# solohm.net
KiCad netlist of a schematic drawn in EAGLE
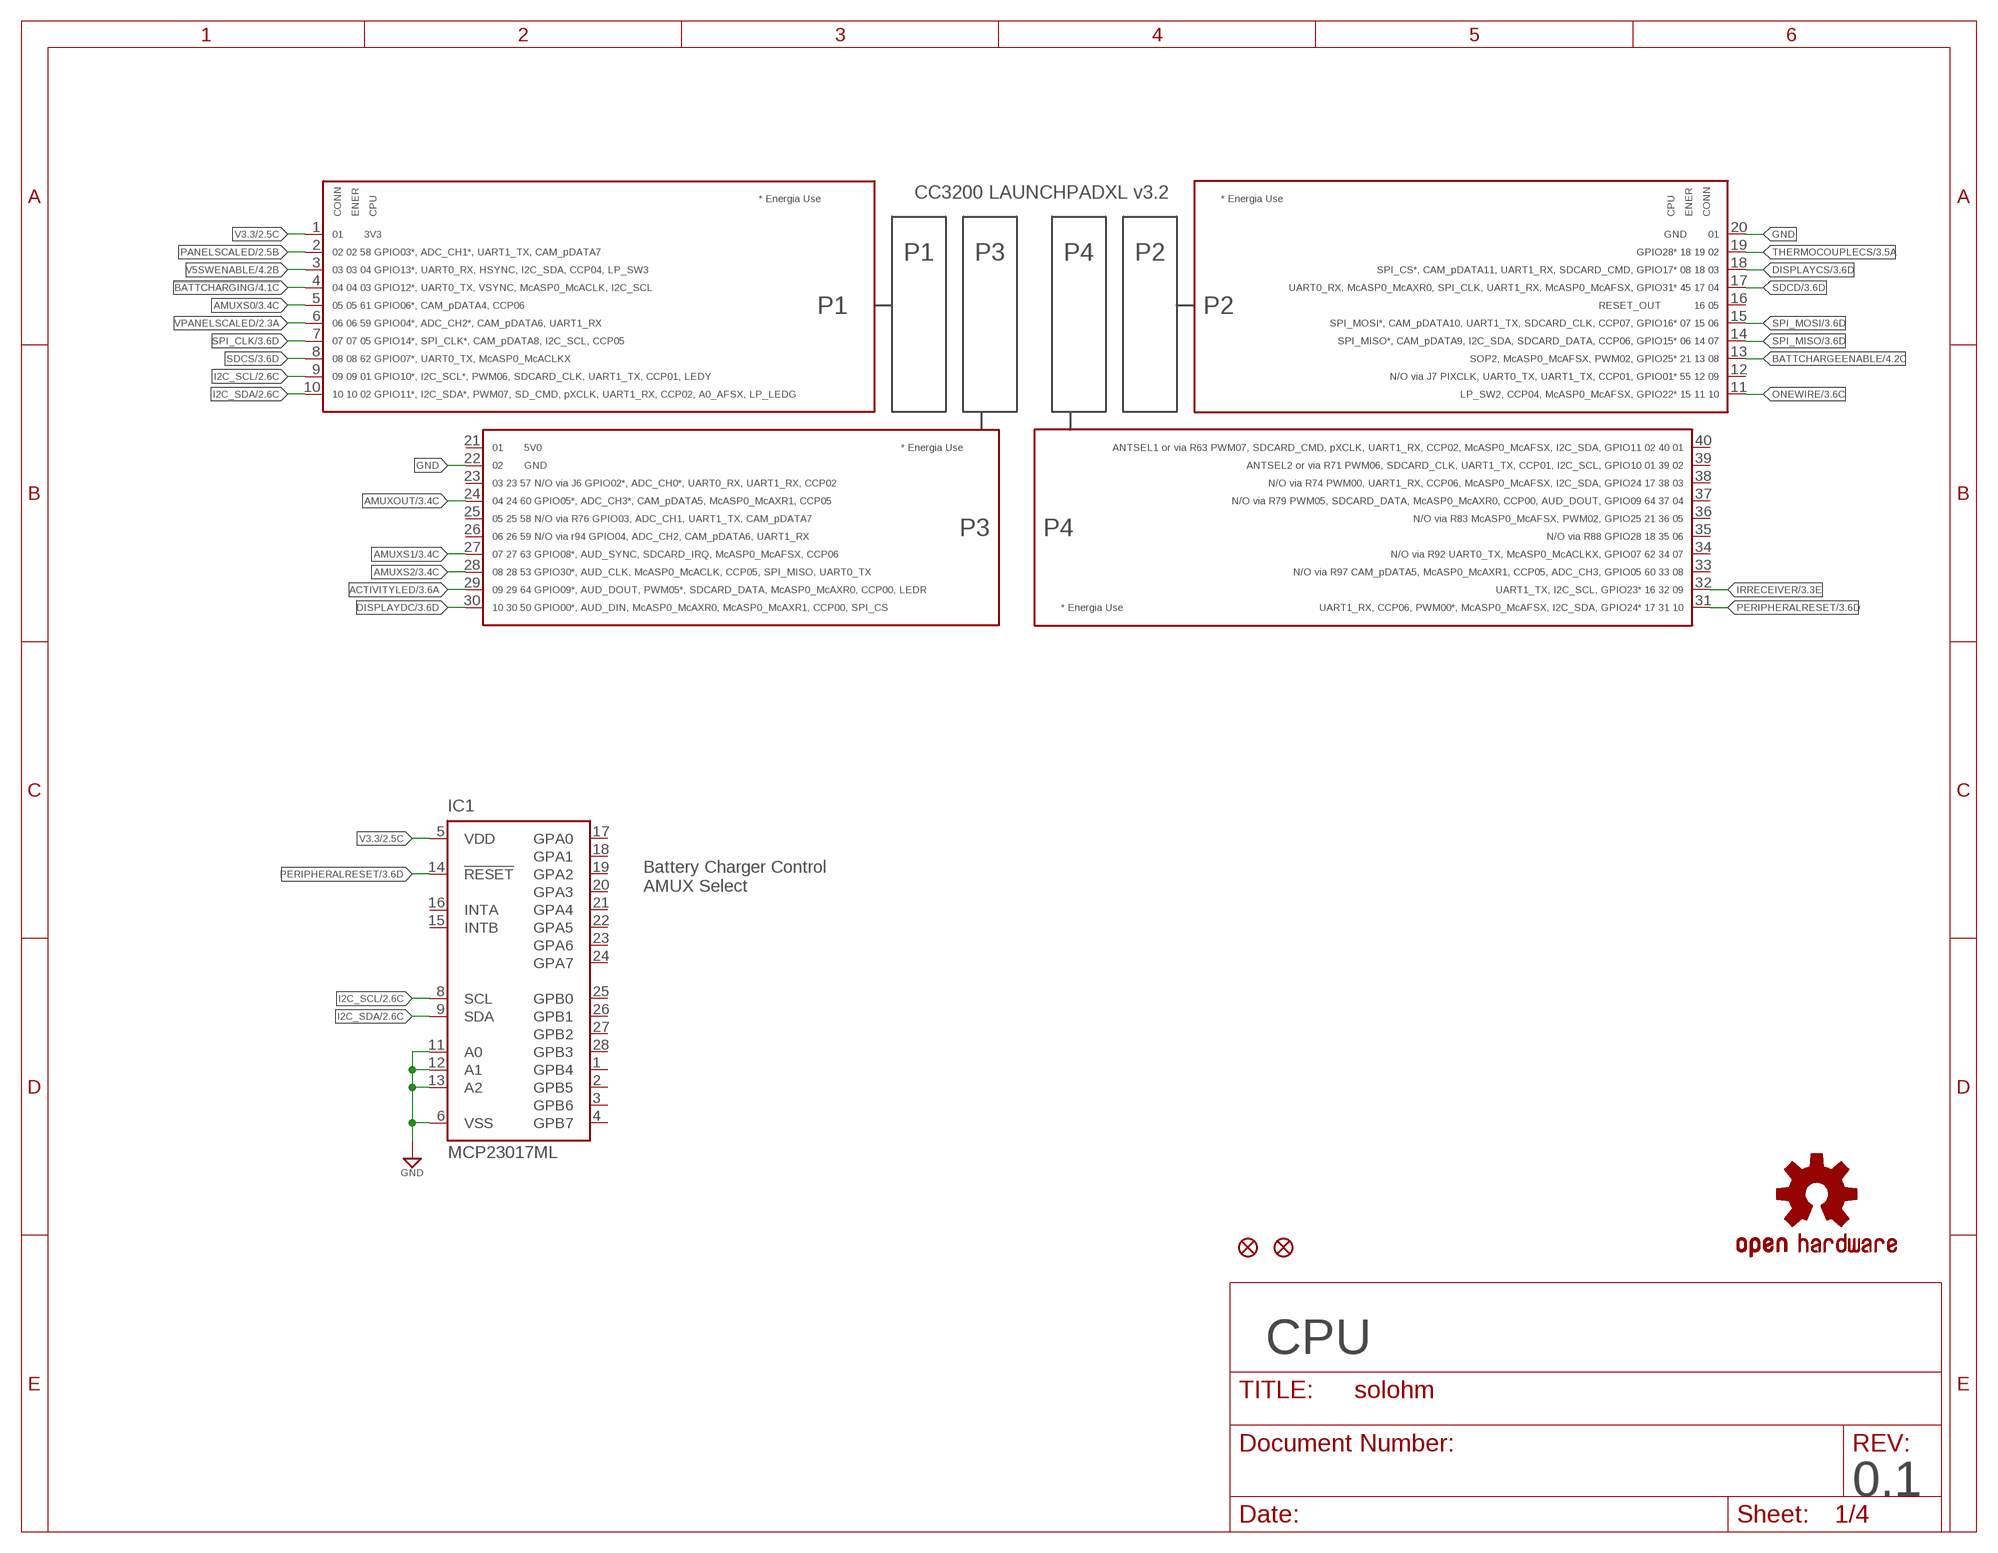
[diagram p0: schematic, sheet 1]
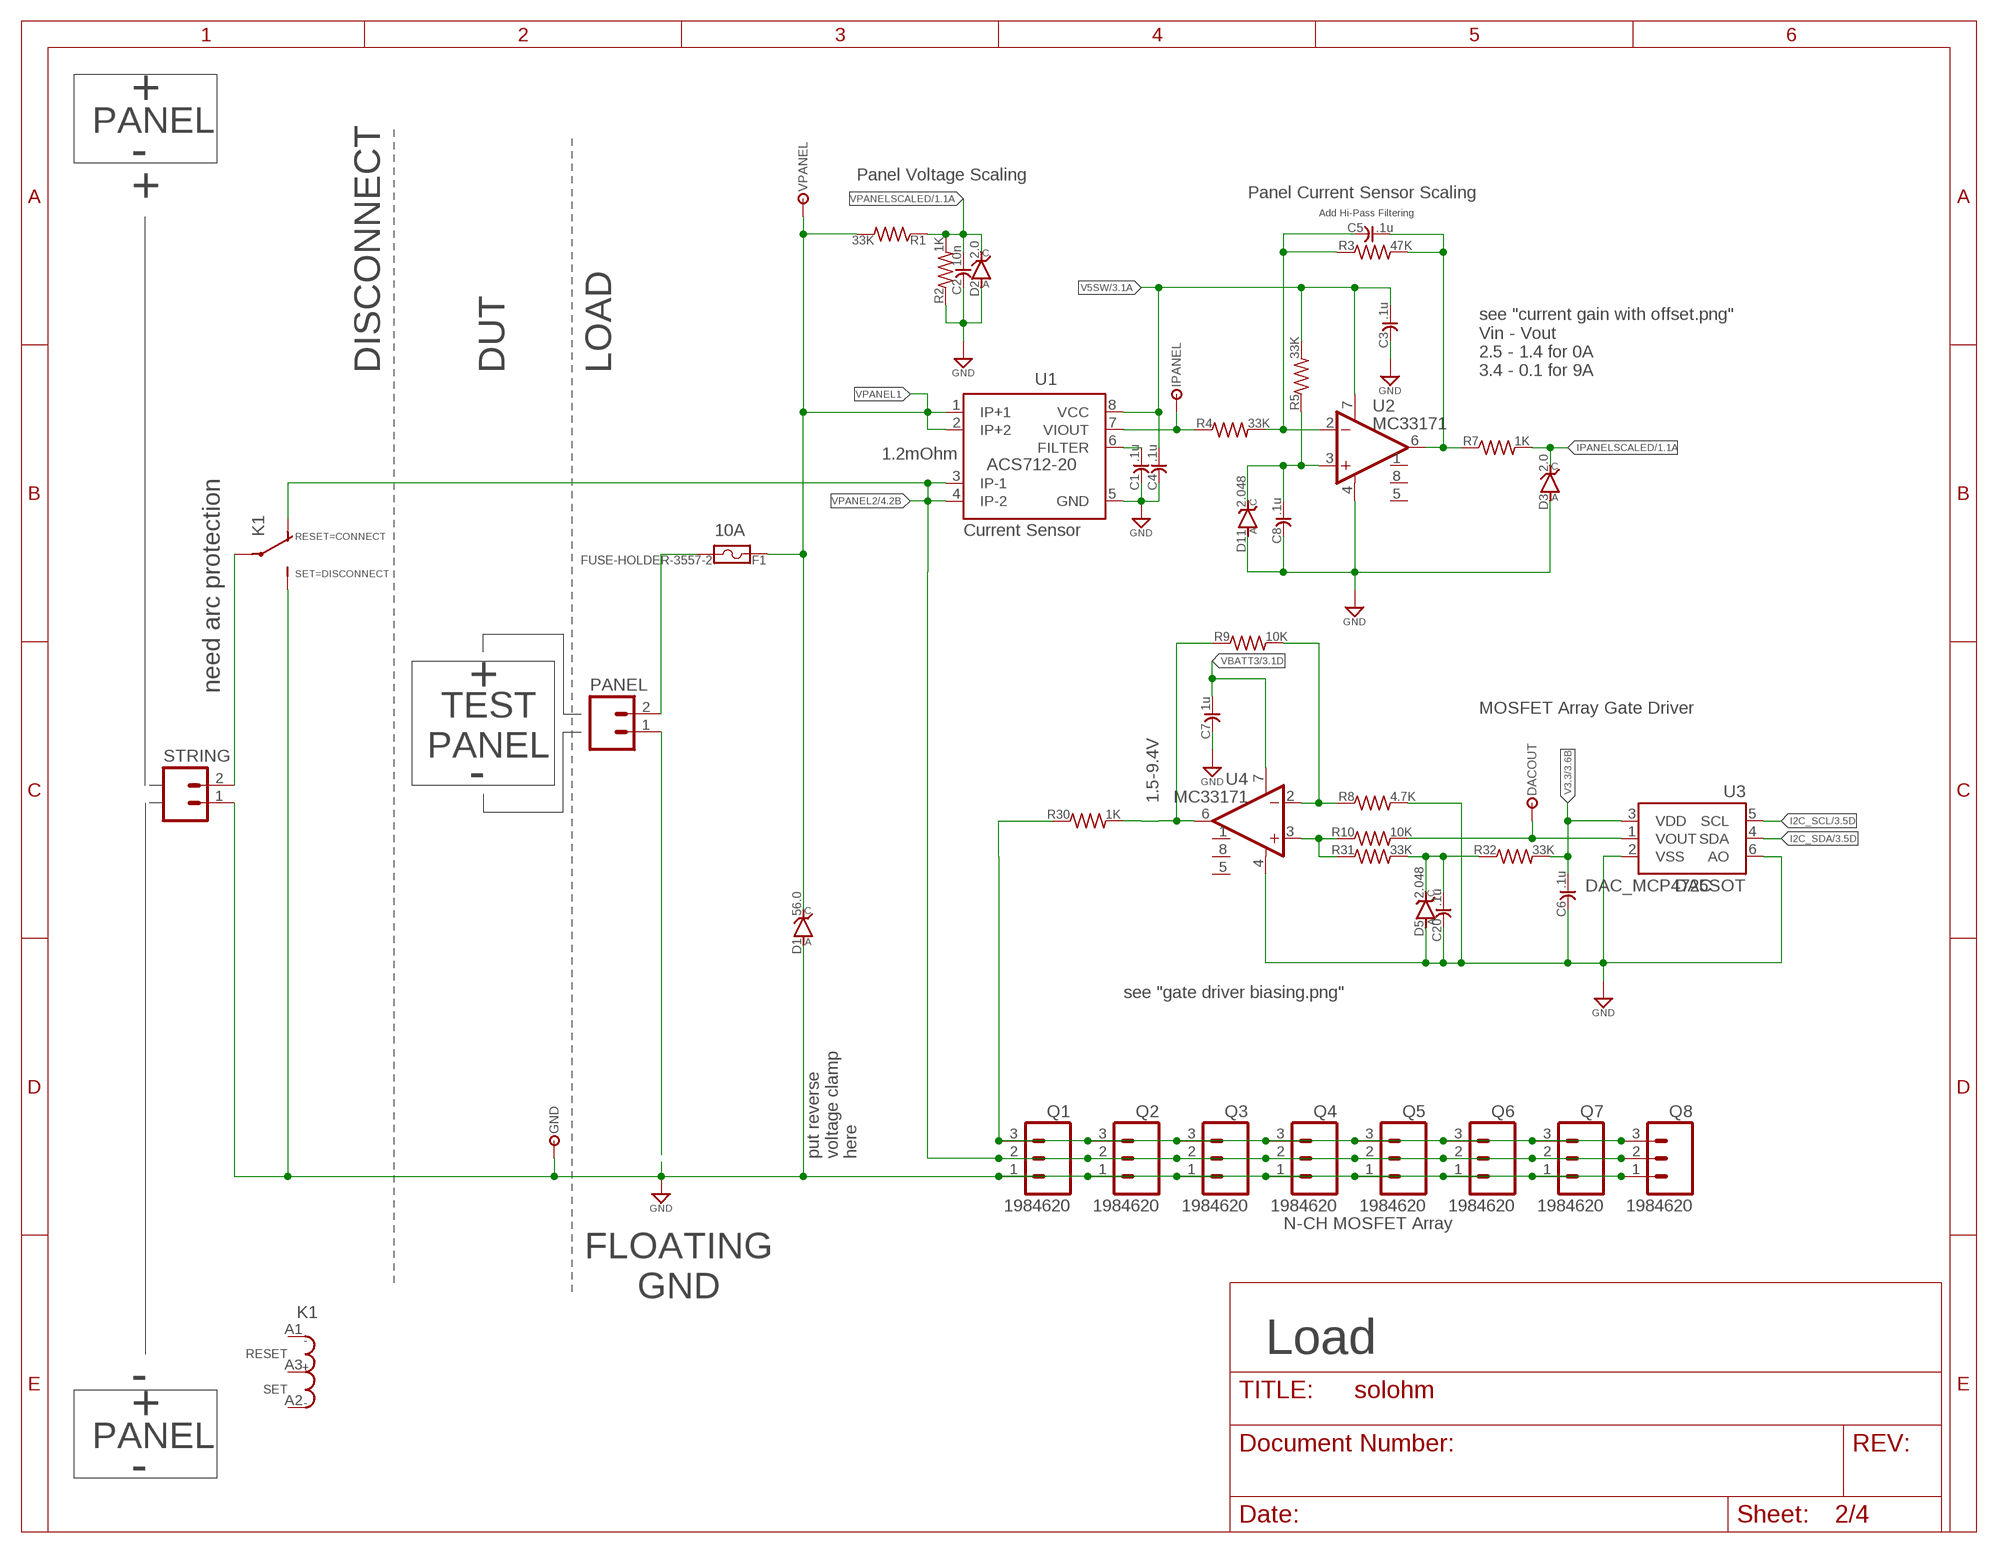
[diagram p1: schematic, sheet 2]
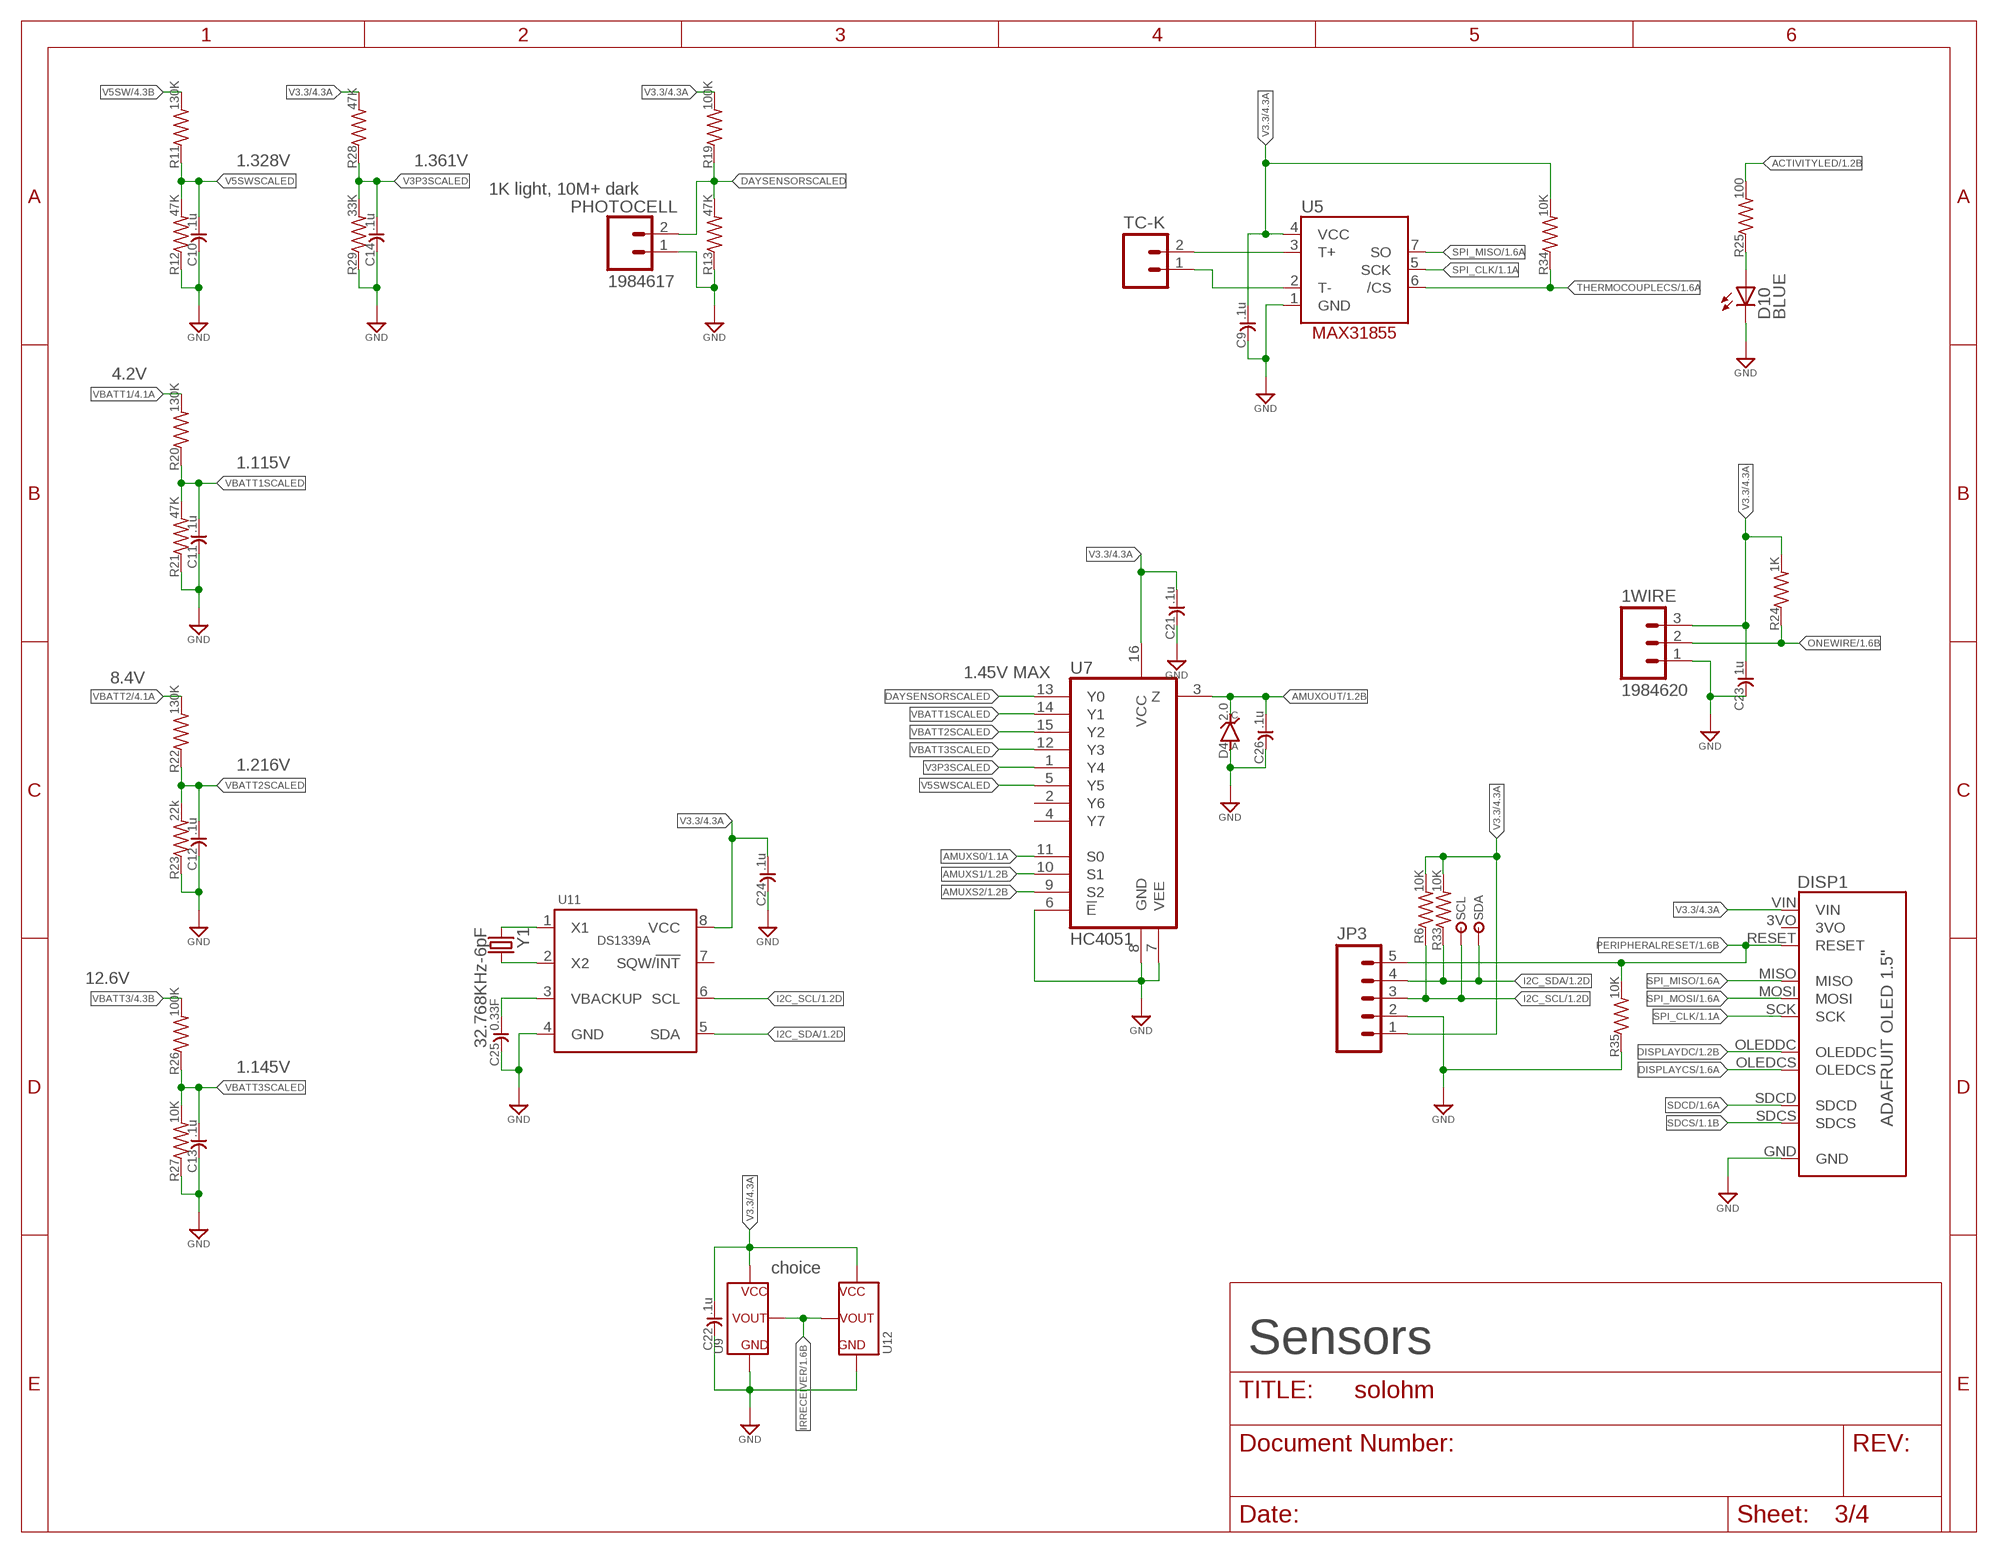
[diagram p2: schematic, sheet 3]
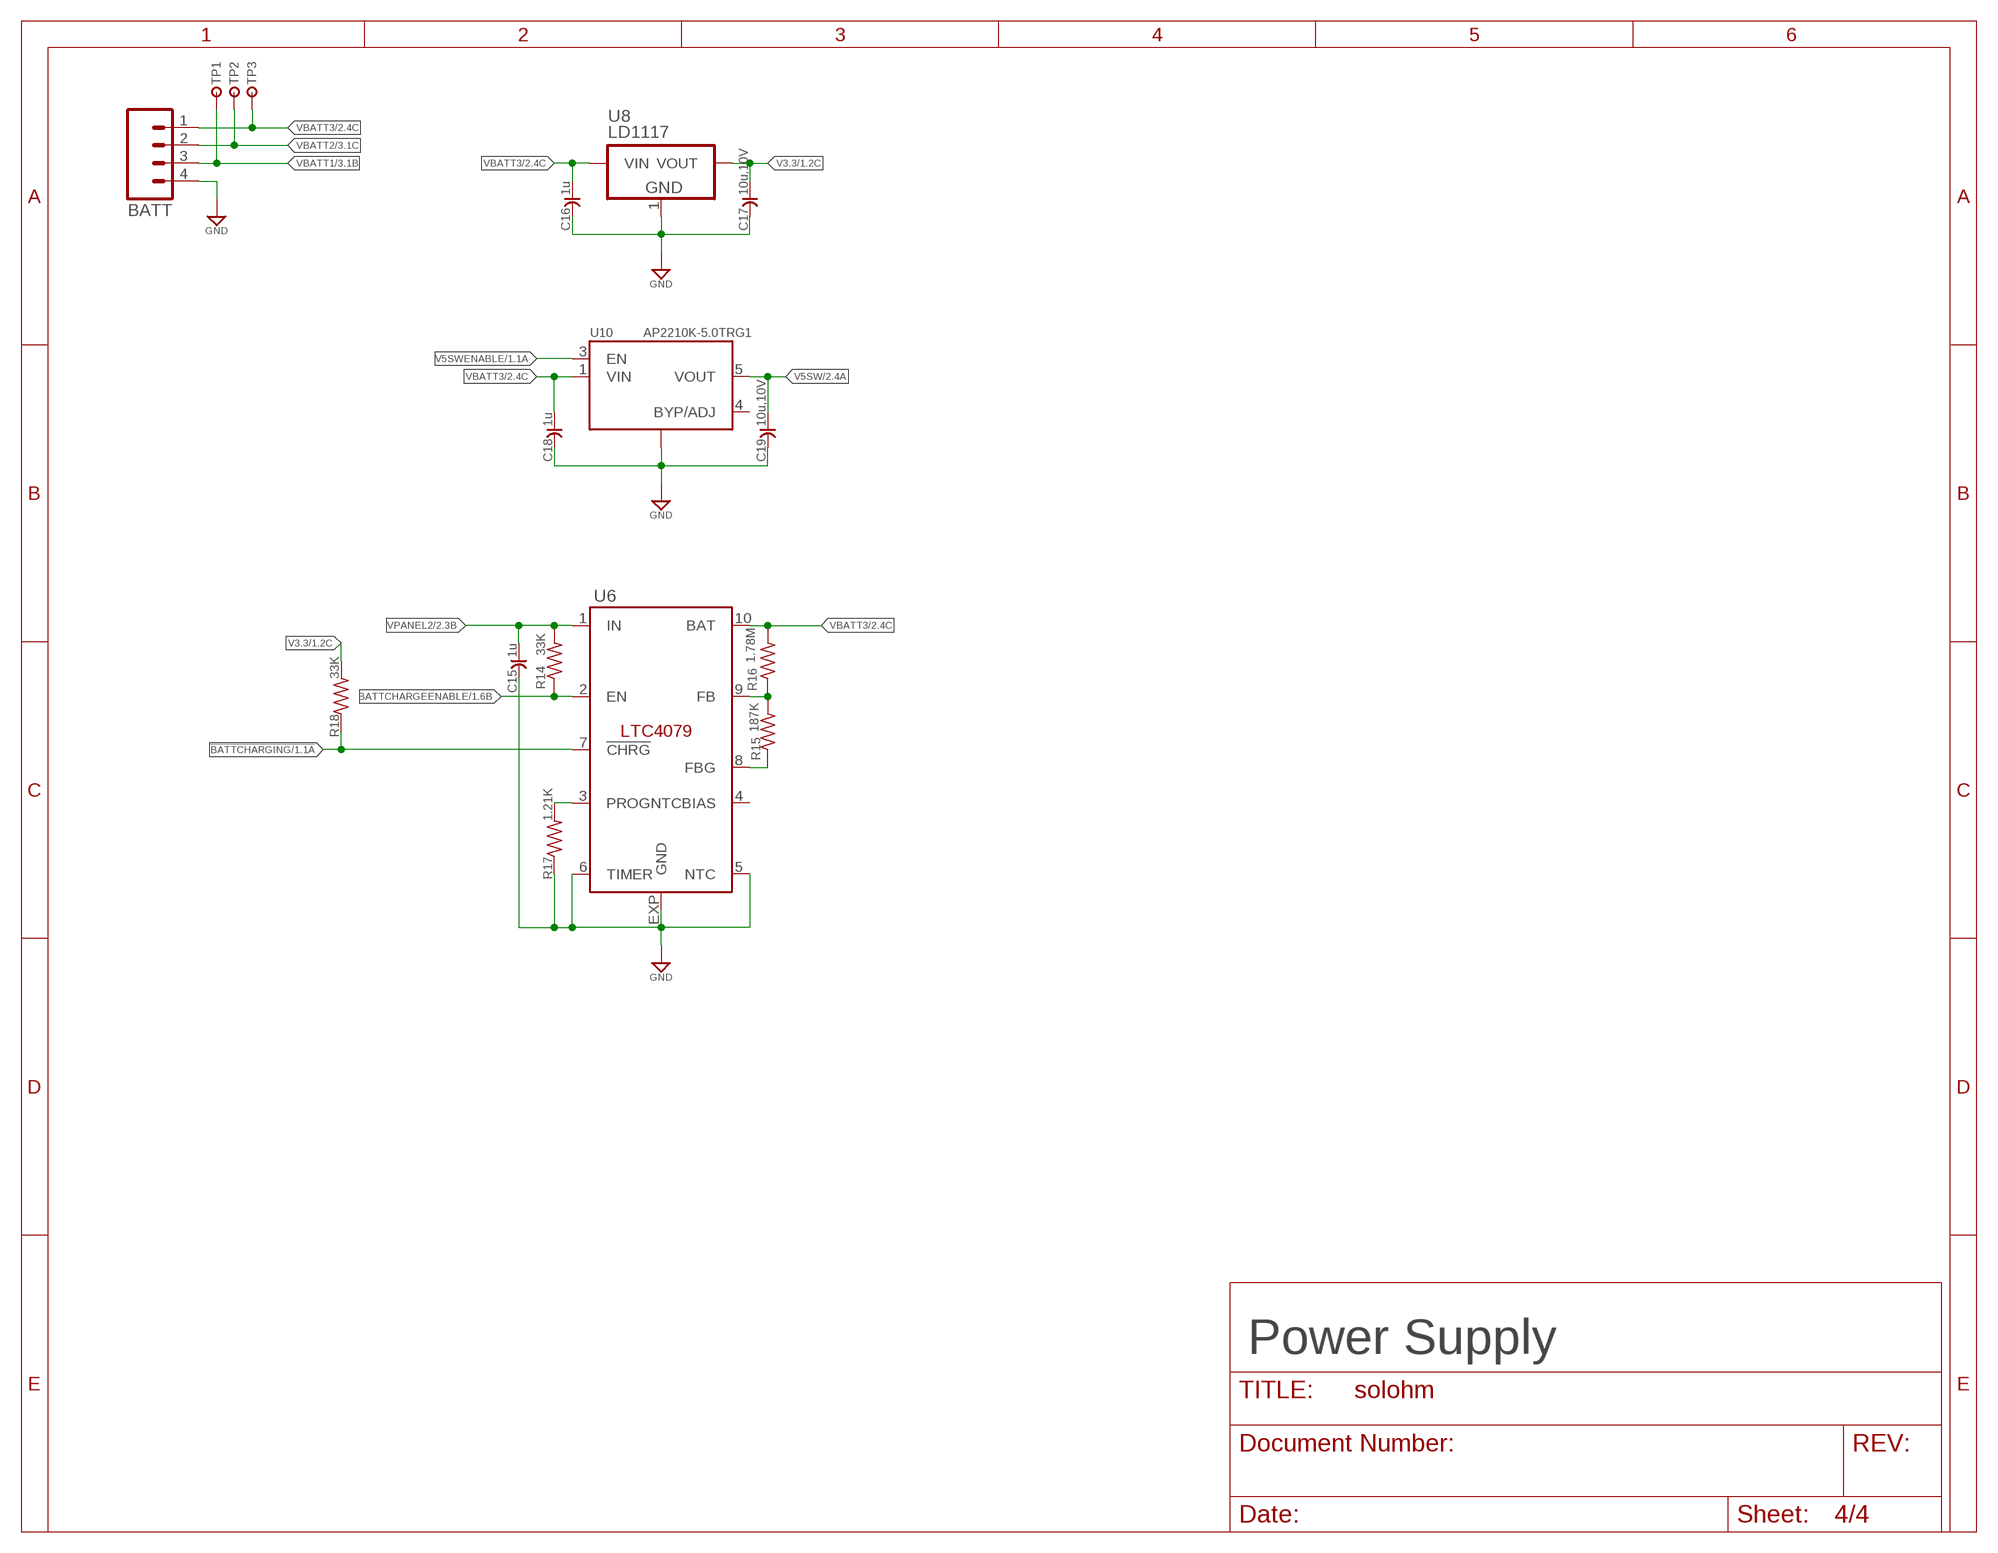
[diagram p3: schematic, sheet 4]

(export (version "E")
  (design (tool "Eeschema 10.0.6"))
  (components
    (comp (ref "A1")
      (value "CC3200-LAUNCHXL-BOOSTERPACK")
      (footprint "eagle-import:CC3200-LAUNCHXL-BOOSTERPACK")
      (libsource (lib "eagle-import") (part "CC3200-LAUNCHXL-BOOSTERPACK"))
    )
    (comp (ref "IC1")
      (value "MCP23017ML")
      (footprint "eagle-import:QFN28-ML_6X6MM")
      (fields (field (name "MF") "MICROCHIP") (field (name "MPN") "MCP23017-E/ML"))
      (libsource (lib "eagle-import") (part "MCP23017ML"))
    )
    (comp (ref "JP1")
      (value "FIDUCIALUFIDUCIAL")
      (footprint "eagle-import:MICRO-FIDUCIAL")
      (libsource (lib "eagle-import") (part "FIDUCIALUFIDUCIAL"))
    )
    (comp (ref "JP2")
      (value "FIDUCIALUFIDUCIAL")
      (footprint "eagle-import:MICRO-FIDUCIAL")
      (libsource (lib "eagle-import") (part "FIDUCIALUFIDUCIAL"))
    )
    (comp (ref "LOGO1")
      (value "LOGO-OSHWL")
      (footprint "eagle-import:LOGO-OSHW-L")
      (libsource (lib "eagle-import") (part "LOGO-OSHWL"))
    )
    (comp (ref "1WIRE")
      (value "1984620")
      (footprint "eagle-import:1984620")
      (libsource (lib "eagle-import") (part "1984620"))
    )
    (comp (ref "C9")
      (value ".1u")
      (footprint "eagle-import:C0603")
      (libsource (lib "eagle-import") (part "C-USC0603"))
    )
    (comp (ref "C10")
      (value ".1u")
      (footprint "eagle-import:C0603")
      (libsource (lib "eagle-import") (part "C-USC0603"))
    )
    (comp (ref "C11")
      (value ".1u")
      (footprint "eagle-import:C0603")
      (libsource (lib "eagle-import") (part "C-USC0603"))
    )
    (comp (ref "C12")
      (value ".1u")
      (footprint "eagle-import:C0603")
      (libsource (lib "eagle-import") (part "C-USC0603"))
    )
    (comp (ref "C13")
      (value ".1u")
      (footprint "eagle-import:C0603")
      (libsource (lib "eagle-import") (part "C-USC0603"))
    )
    (comp (ref "C14")
      (value ".1u")
      (footprint "eagle-import:C0603")
      (libsource (lib "eagle-import") (part "C-USC0603"))
    )
    (comp (ref "C21")
      (value ".1u")
      (footprint "eagle-import:C0603")
      (libsource (lib "eagle-import") (part "C-USC0603"))
    )
    (comp (ref "C22")
      (value ".1u")
      (footprint "eagle-import:C0603")
      (libsource (lib "eagle-import") (part "C-USC0603"))
    )
    (comp (ref "C23")
      (value "1u")
      (footprint "eagle-import:C0603")
      (libsource (lib "eagle-import") (part "C-USC0603"))
    )
    (comp (ref "C24")
      (value ".1u")
      (footprint "eagle-import:C0603")
      (libsource (lib "eagle-import") (part "C-USC0603"))
    )
    (comp (ref "C25")
      (value "0.33F")
      (footprint "eagle-import:CAP-SUPER-AXIAL-10MM")
      (libsource (lib "eagle-import") (part "C-SUPER-10MM"))
    )
    (comp (ref "C26")
      (value ".1u")
      (footprint "eagle-import:C0603")
      (libsource (lib "eagle-import") (part "C-USC0603"))
    )
    (comp (ref "D4")
      (value "2.0")
      (footprint "eagle-import:SOD-323")
      (libsource (lib "eagle-import") (part "ZENER-SOD323"))
    )
    (comp (ref "D10")
      (value "BLUE")
      (footprint "eagle-import:LED0805")
      (libsource (lib "eagle-import") (part "LED-0805"))
    )
    (comp (ref "DISP1")
      (value "BOARD-DISP-ADAFRUIT-OLED-1.5")
      (footprint "eagle-import:BOARD-DISP-ADAFRUIT-OLED-1.5")
      (libsource (lib "eagle-import") (part "BOARD-DISP-ADAFRUIT-OLED-1.5"))
    )
    (comp (ref "JP3")
      (value "M05PTH")
      (footprint "eagle-import:1X05")
      (libsource (lib "eagle-import") (part "M05PTH"))
    )
    (comp (ref "PHOTOCELL")
      (value "1984617")
      (footprint "eagle-import:1984617")
      (libsource (lib "eagle-import") (part "1984617"))
    )
    (comp (ref "R6")
      (value "10K")
      (footprint "eagle-import:R0603")
      (libsource (lib "eagle-import") (part "R-US_R0603"))
    )
    (comp (ref "R11")
      (value "130K")
      (footprint "eagle-import:R0603")
      (libsource (lib "eagle-import") (part "R-US_R0603"))
    )
    (comp (ref "R12")
      (value "47K")
      (footprint "eagle-import:R0603")
      (libsource (lib "eagle-import") (part "R-US_R0603"))
    )
    (comp (ref "R13")
      (value "47K")
      (footprint "eagle-import:R0603")
      (libsource (lib "eagle-import") (part "R-US_R0603"))
    )
    (comp (ref "R19")
      (value "100K")
      (footprint "eagle-import:R0603")
      (libsource (lib "eagle-import") (part "R-US_R0603"))
    )
    (comp (ref "R20")
      (value "130K")
      (footprint "eagle-import:R0603")
      (libsource (lib "eagle-import") (part "R-US_R0603"))
    )
    (comp (ref "R21")
      (value "47K")
      (footprint "eagle-import:R0603")
      (libsource (lib "eagle-import") (part "R-US_R0603"))
    )
    (comp (ref "R22")
      (value "130K")
      (footprint "eagle-import:R0603")
      (libsource (lib "eagle-import") (part "R-US_R0603"))
    )
    (comp (ref "R23")
      (value "22k")
      (footprint "eagle-import:R0603")
      (libsource (lib "eagle-import") (part "R-US_R0603"))
    )
    (comp (ref "R24")
      (value "1K")
      (footprint "eagle-import:R0603")
      (libsource (lib "eagle-import") (part "R-US_R0603"))
    )
    (comp (ref "R25")
      (value "100")
      (footprint "eagle-import:R0603")
      (libsource (lib "eagle-import") (part "R-US_R0603"))
    )
    (comp (ref "R26")
      (value "100K")
      (footprint "eagle-import:R0603")
      (libsource (lib "eagle-import") (part "R-US_R0603"))
    )
    (comp (ref "R27")
      (value "10K")
      (footprint "eagle-import:R0603")
      (libsource (lib "eagle-import") (part "R-US_R0603"))
    )
    (comp (ref "R28")
      (value "47K")
      (footprint "eagle-import:R0603")
      (libsource (lib "eagle-import") (part "R-US_R0603"))
    )
    (comp (ref "R29")
      (value "33K")
      (footprint "eagle-import:R0603")
      (libsource (lib "eagle-import") (part "R-US_R0603"))
    )
    (comp (ref "R33")
      (value "10K")
      (footprint "eagle-import:R0603")
      (libsource (lib "eagle-import") (part "R-US_R0603"))
    )
    (comp (ref "R34")
      (value "10K")
      (footprint "eagle-import:R0603")
      (libsource (lib "eagle-import") (part "R-US_R0603"))
    )
    (comp (ref "R35")
      (value "10K")
      (footprint "eagle-import:R0603")
      (libsource (lib "eagle-import") (part "R-US_R0603"))
    )
    (comp (ref "SCL")
      (value "TESTPOINTTHRU")
      (footprint "eagle-import:TPTHRU")
      (libsource (lib "eagle-import") (part "TESTPOINTTHRU"))
    )
    (comp (ref "SDA")
      (value "TESTPOINTTHRU")
      (footprint "eagle-import:TPTHRU")
      (libsource (lib "eagle-import") (part "TESTPOINTTHRU"))
    )
    (comp (ref "TC-K")
      (value "M02-1984617")
      (footprint "eagle-import:1984617")
      (libsource (lib "eagle-import") (part "M02-1984617"))
    )
    (comp (ref "U5")
      (value "THERMOCOUPLE-MAX31855")
      (footprint "eagle-import:SO08")
      (libsource (lib "eagle-import") (part "THERMOCOUPLE-MAX31855"))
    )
    (comp (ref "U7")
      (value "HC4051")
      (footprint "eagle-import:SO16")
      (libsource (lib "eagle-import") (part "HC4051"))
    )
    (comp (ref "U9")
      (value "IRDETECTOR-THRU")
      (footprint "eagle-import:IRDETECTOR-THRU")
      (libsource (lib "eagle-import") (part "IRDETECTOR-THRU"))
    )
    (comp (ref "U11")
      (value "RTC-DS1339A")
      (footprint "eagle-import:MSOP8")
      (libsource (lib "eagle-import") (part "RTC-DS1339A"))
    )
    (comp (ref "U12")
      (value "IRDETECTOR-TSOP6X")
      (footprint "eagle-import:IRDETECTOR-TSOP6X")
      (libsource (lib "eagle-import") (part "IRDETECTOR-TSOP6X"))
    )
    (comp (ref "Y1")
      (value "32.768KHz-6pF")
      (footprint "eagle-import:ABS25")
      (libsource (lib "eagle-import") (part "CRYSTAL32-SMDABS25"))
    )
    (comp (ref "C1")
      (value ".1u")
      (footprint "eagle-import:C0603")
      (libsource (lib "eagle-import") (part "C-USC0603"))
    )
    (comp (ref "C2")
      (value "10n")
      (footprint "eagle-import:C0603")
      (libsource (lib "eagle-import") (part "C-USC0603"))
    )
    (comp (ref "C3")
      (value ".1u")
      (footprint "eagle-import:C0603")
      (libsource (lib "eagle-import") (part "C-USC0603"))
    )
    (comp (ref "C4")
      (value ".1u")
      (footprint "eagle-import:C0603")
      (libsource (lib "eagle-import") (part "C-USC0603"))
    )
    (comp (ref "C5")
      (value ".1u")
      (footprint "eagle-import:C0603")
      (libsource (lib "eagle-import") (part "C-USC0603"))
    )
    (comp (ref "C6")
      (value ".1u")
      (footprint "eagle-import:C0603")
      (libsource (lib "eagle-import") (part "C-USC0603"))
    )
    (comp (ref "C7")
      (value "1u")
      (footprint "eagle-import:C0603")
      (libsource (lib "eagle-import") (part "C-USC0603"))
    )
    (comp (ref "C8")
      (value ".1u")
      (footprint "eagle-import:C0603")
      (libsource (lib "eagle-import") (part "C-USC0603"))
    )
    (comp (ref "C20")
      (value ".1u")
      (footprint "eagle-import:C0603")
      (libsource (lib "eagle-import") (part "C-USC0603"))
    )
    (comp (ref "D1")
      (value "56.0")
      (footprint "eagle-import:SOD-323")
      (libsource (lib "eagle-import") (part "ZENER-SOD323"))
    )
    (comp (ref "D2")
      (value "2.0")
      (footprint "eagle-import:SOD-323")
      (libsource (lib "eagle-import") (part "ZENER-SOD323"))
    )
    (comp (ref "D3")
      (value "2.0")
      (footprint "eagle-import:SOD-323")
      (libsource (lib "eagle-import") (part "ZENER-SOD323"))
    )
    (comp (ref "D5")
      (value "2.048")
      (footprint "eagle-import:SOT23-3")
      (libsource (lib "eagle-import") (part "ZENER-3TERM-SOT23-3"))
    )
    (comp (ref "D11")
      (value "2.048")
      (footprint "eagle-import:SOT23-3")
      (libsource (lib "eagle-import") (part "ZENER-3TERM-SOT23-3"))
    )
    (comp (ref "DACOUT")
      (value "TESTPOINTTHRU")
      (footprint "eagle-import:TPTHRU")
      (libsource (lib "eagle-import") (part "TESTPOINTTHRU"))
    )
    (comp (ref "F1")
      (value "FUSE-HOLDER-3557-2")
      (footprint "eagle-import:3557-2")
      (libsource (lib "eagle-import") (part "FUSE-HOLDER-3557-2"))
    )
    (comp (ref "GND")
      (value "TESTPOINTTHRU")
      (footprint "eagle-import:TPTHRU")
      (libsource (lib "eagle-import") (part "TESTPOINTTHRU"))
    )
    (comp (ref "IPANEL")
      (value "TESTPOINTTHRU")
      (footprint "eagle-import:TPTHRU")
      (libsource (lib "eagle-import") (part "TESTPOINTTHRU"))
    )
    (comp (ref "K1")
      (value "RELAY-LATCHING-DUAL-1FORMC-5MM-16A")
      (footprint "eagle-import:RELAY-1FORMC-5MM-16A")
      (libsource (lib "eagle-import") (part "RELAY-LATCHING-DUAL-1FORMC-5MM-16A"))
    )
    (comp (ref "PANEL")
      (value "M02-6.35MM")
      (footprint "eagle-import:OSTT702")
      (libsource (lib "eagle-import") (part "M02-6.35MM"))
    )
    (comp (ref "Q1")
      (value "1984620")
      (footprint "eagle-import:1984620")
      (libsource (lib "eagle-import") (part "1984620"))
    )
    (comp (ref "Q2")
      (value "1984620")
      (footprint "eagle-import:1984620")
      (libsource (lib "eagle-import") (part "1984620"))
    )
    (comp (ref "Q3")
      (value "1984620")
      (footprint "eagle-import:1984620")
      (libsource (lib "eagle-import") (part "1984620"))
    )
    (comp (ref "Q4")
      (value "1984620")
      (footprint "eagle-import:1984620")
      (libsource (lib "eagle-import") (part "1984620"))
    )
    (comp (ref "Q5")
      (value "1984620")
      (footprint "eagle-import:1984620")
      (libsource (lib "eagle-import") (part "1984620"))
    )
    (comp (ref "Q6")
      (value "1984620")
      (footprint "eagle-import:1984620")
      (libsource (lib "eagle-import") (part "1984620"))
    )
    (comp (ref "Q7")
      (value "1984620")
      (footprint "eagle-import:1984620")
      (libsource (lib "eagle-import") (part "1984620"))
    )
    (comp (ref "Q8")
      (value "1984620")
      (footprint "eagle-import:1984620")
      (libsource (lib "eagle-import") (part "1984620"))
    )
    (comp (ref "R1")
      (value "33K")
      (footprint "eagle-import:R0603")
      (libsource (lib "eagle-import") (part "R-US_R0603"))
    )
    (comp (ref "R2")
      (value "1K")
      (footprint "eagle-import:R0603")
      (libsource (lib "eagle-import") (part "R-US_R0603"))
    )
    (comp (ref "R3")
      (value "47K")
      (footprint "eagle-import:R0603")
      (libsource (lib "eagle-import") (part "R-US_R0603"))
    )
    (comp (ref "R4")
      (value "33K")
      (footprint "eagle-import:R0603")
      (libsource (lib "eagle-import") (part "R-US_R0603"))
    )
    (comp (ref "R5")
      (value "33K")
      (footprint "eagle-import:R0603")
      (libsource (lib "eagle-import") (part "R-US_R0603"))
    )
    (comp (ref "R7")
      (value "1K")
      (footprint "eagle-import:R0603")
      (libsource (lib "eagle-import") (part "R-US_R0603"))
    )
    (comp (ref "R8")
      (value "4.7K")
      (footprint "eagle-import:R0603")
      (libsource (lib "eagle-import") (part "R-US_R0603"))
    )
    (comp (ref "R9")
      (value "10K")
      (footprint "eagle-import:R0603")
      (libsource (lib "eagle-import") (part "R-US_R0603"))
    )
    (comp (ref "R10")
      (value "10K")
      (footprint "eagle-import:R0603")
      (libsource (lib "eagle-import") (part "R-US_R0603"))
    )
    (comp (ref "R30")
      (value "1K")
      (footprint "eagle-import:R0603")
      (libsource (lib "eagle-import") (part "R-US_R0603"))
    )
    (comp (ref "R31")
      (value "33K")
      (footprint "eagle-import:R0603")
      (libsource (lib "eagle-import") (part "R-US_R0603"))
    )
    (comp (ref "R32")
      (value "33K")
      (footprint "eagle-import:R0603")
      (libsource (lib "eagle-import") (part "R-US_R0603"))
    )
    (comp (ref "STRING")
      (value "M02-6.35MM")
      (footprint "eagle-import:OSTT702")
      (libsource (lib "eagle-import") (part "M02-6.35MM"))
    )
    (comp (ref "U1")
      (value "20")
      (footprint "eagle-import:SOIC08")
      (libsource (lib "eagle-import") (part "ACS712"))
    )
    (comp (ref "U2")
      (value "MC33171")
      (footprint "eagle-import:SO08")
      (libsource (lib "eagle-import") (part "OPAMP-SO08LM"))
    )
    (comp (ref "U3")
      (value "DAC_MCP4725SOT")
      (footprint "eagle-import:SOT23-6")
      (libsource (lib "eagle-import") (part "DAC_MCP4725SOT"))
    )
    (comp (ref "U4")
      (value "MC33171")
      (footprint "eagle-import:SO08")
      (libsource (lib "eagle-import") (part "OPAMP-SO08LM"))
    )
    (comp (ref "VPANEL")
      (value "TESTPOINTTHRU")
      (footprint "eagle-import:TPTHRU")
      (libsource (lib "eagle-import") (part "TESTPOINTTHRU"))
    )
    (comp (ref "BATT")
      (value "M04-B4B-XH-VERT")
      (footprint "eagle-import:JST-B4B-XH-VERT")
      (libsource (lib "eagle-import") (part "M04-B4B-XH-VERT"))
    )
    (comp (ref "C15")
      (value "1u")
      (footprint "eagle-import:C0603")
      (libsource (lib "eagle-import") (part "C-USC0603"))
    )
    (comp (ref "C16")
      (value "1u")
      (footprint "eagle-import:C0603")
      (libsource (lib "eagle-import") (part "C-USC0603"))
    )
    (comp (ref "C17")
      (value "10u,10V")
      (footprint "eagle-import:C0805")
      (libsource (lib "eagle-import") (part "C-USC0805"))
    )
    (comp (ref "C18")
      (value "1u")
      (footprint "eagle-import:C0603")
      (libsource (lib "eagle-import") (part "C-USC0603"))
    )
    (comp (ref "C19")
      (value "10u,10V")
      (footprint "eagle-import:C0805")
      (libsource (lib "eagle-import") (part "C-USC0805"))
    )
    (comp (ref "R14")
      (value "33K")
      (footprint "eagle-import:R0603")
      (libsource (lib "eagle-import") (part "R-US_R0603"))
    )
    (comp (ref "R15")
      (value "187K")
      (footprint "eagle-import:R0603")
      (libsource (lib "eagle-import") (part "R-US_R0603"))
    )
    (comp (ref "R16")
      (value "1.78M")
      (footprint "eagle-import:R0603")
      (libsource (lib "eagle-import") (part "R-US_R0603"))
    )
    (comp (ref "R17")
      (value "1.21K")
      (footprint "eagle-import:R0603")
      (libsource (lib "eagle-import") (part "R-US_R0603"))
    )
    (comp (ref "R18")
      (value "33K")
      (footprint "eagle-import:R0603")
      (libsource (lib "eagle-import") (part "R-US_R0603"))
    )
    (comp (ref "TP1")
      (value "TESTPOINT0.5")
      (footprint "eagle-import:TP0.5R")
      (libsource (lib "eagle-import") (part "TESTPOINT0.5"))
    )
    (comp (ref "TP2")
      (value "TESTPOINT0.5")
      (footprint "eagle-import:TP0.5R")
      (libsource (lib "eagle-import") (part "TESTPOINT0.5"))
    )
    (comp (ref "TP3")
      (value "TESTPOINT0.5")
      (footprint "eagle-import:TP0.5R")
      (libsource (lib "eagle-import") (part "TESTPOINT0.5"))
    )
    (comp (ref "U6")
      (value "BATTCHARGER-LTC4079")
      (footprint "eagle-import:DFN10-3X3")
      (libsource (lib "eagle-import") (part "BATTCHARGER-LTC4079"))
    )
    (comp (ref "U8")
      (value "LD1117")
      (footprint "eagle-import:SOT-223")
      (libsource (lib "eagle-import") (part "VOLTAGEREG-SOT-223"))
    )
    (comp (ref "U10")
      (value "AP2210K-5.0TRG1")
      (footprint "eagle-import:SOT23-5")
      (libsource (lib "eagle-import") (part "VOLTAGEREG-ENABLE"))
    )
  )
  (nets
    (net (code "1") (name "ACTIVITYLED") (class "Default")
      (node (ref "A1") (pin "29") (pinfunction "P$29_29") (pintype "bidirectional"))
      (node (ref "R25") (pin "2") (pinfunction "2_2") (pintype "passive"))
    )
    (net (code "2") (name "AMUXOUT") (class "Default")
      (node (ref "A1") (pin "24") (pinfunction "P$24_24") (pintype "bidirectional"))
      (node (ref "C26") (pin "1") (pinfunction "1_1") (pintype "passive"))
      (node (ref "D4") (pin "C") (pinfunction "C_C") (pintype "bidirectional"))
      (node (ref "U7") (pin "3") (pinfunction "Z_3") (pintype "bidirectional"))
    )
    (net (code "3") (name "AMUXS0") (class "Default")
      (node (ref "A1") (pin "5") (pinfunction "P$5_5") (pintype "bidirectional"))
      (node (ref "U7") (pin "11") (pinfunction "S0_11") (pintype "input"))
    )
    (net (code "4") (name "AMUXS1") (class "Default")
      (node (ref "A1") (pin "27") (pinfunction "P$27_27") (pintype "bidirectional"))
      (node (ref "U7") (pin "10") (pinfunction "S1_10") (pintype "input"))
    )
    (net (code "5") (name "AMUXS2") (class "Default")
      (node (ref "A1") (pin "28") (pinfunction "P$28_28") (pintype "bidirectional"))
      (node (ref "U7") (pin "9") (pinfunction "S2_9") (pintype "input"))
    )
    (net (code "6") (name "BATTCHARGEENABLE") (class "Default")
      (node (ref "A1") (pin "13") (pinfunction "P$13_13") (pintype "bidirectional"))
      (node (ref "R14") (pin "1") (pinfunction "1_1") (pintype "passive"))
      (node (ref "U6") (pin "2") (pinfunction "EN_2") (pintype "bidirectional"))
    )
    (net (code "7") (name "DAYSENSORSCALED") (class "Default")
      (node (ref "PHOTOCELL") (pin "2") (pinfunction "2_2") (pintype "passive"))
      (node (ref "R13") (pin "2") (pinfunction "2_2") (pintype "passive"))
      (node (ref "R19") (pin "1") (pinfunction "1_1") (pintype "passive"))
      (node (ref "U7") (pin "13") (pinfunction "Y0_13") (pintype "bidirectional"))
    )
    (net (code "8") (name "DISPLAYCS") (class "Default")
      (node (ref "A1") (pin "18") (pinfunction "P$18_18") (pintype "bidirectional"))
      (node (ref "DISP1") (pin "OLEDCS") (pinfunction "OLEDCS_OLEDCS") (pintype "bidirectional"))
    )
    (net (code "9") (name "DISPLAYDC") (class "Default")
      (node (ref "A1") (pin "30") (pinfunction "P$30_30") (pintype "bidirectional"))
      (node (ref "DISP1") (pin "OLEDDC") (pinfunction "OLEDDC_OLEDDC") (pintype "bidirectional"))
    )
    (net (code "10") (name "GND") (class "Default")
      (node (ref "1WIRE") (pin "1") (pinfunction "1_1") (pintype "passive"))
      (node (ref "A1") (pin "20") (pinfunction "P$20_20") (pintype "bidirectional"))
      (node (ref "A1") (pin "22") (pinfunction "P$22_22") (pintype "bidirectional"))
      (node (ref "BATT") (pin "4") (pinfunction "4_4") (pintype "passive"))
      (node (ref "C1") (pin "2") (pinfunction "2_2") (pintype "passive"))
      (node (ref "C10") (pin "2") (pinfunction "2_2") (pintype "passive"))
      (node (ref "C11") (pin "2") (pinfunction "2_2") (pintype "passive"))
      (node (ref "C12") (pin "2") (pinfunction "2_2") (pintype "passive"))
      (node (ref "C13") (pin "2") (pinfunction "2_2") (pintype "passive"))
      (node (ref "C14") (pin "2") (pinfunction "2_2") (pintype "passive"))
      (node (ref "C15") (pin "2") (pinfunction "2_2") (pintype "passive"))
      (node (ref "C16") (pin "2") (pinfunction "2_2") (pintype "passive"))
      (node (ref "C17") (pin "2") (pinfunction "2_2") (pintype "passive"))
      (node (ref "C18") (pin "2") (pinfunction "2_2") (pintype "passive"))
      (node (ref "C19") (pin "2") (pinfunction "2_2") (pintype "passive"))
      (node (ref "C2") (pin "2") (pinfunction "2_2") (pintype "passive"))
      (node (ref "C20") (pin "2") (pinfunction "2_2") (pintype "passive"))
      (node (ref "C21") (pin "2") (pinfunction "2_2") (pintype "passive"))
      (node (ref "C22") (pin "2") (pinfunction "2_2") (pintype "passive"))
      (node (ref "C23") (pin "2") (pinfunction "2_2") (pintype "passive"))
      (node (ref "C24") (pin "2") (pinfunction "2_2") (pintype "passive"))
      (node (ref "C25") (pin "-") (pinfunction "2_-") (pintype "passive"))
      (node (ref "C26") (pin "2") (pinfunction "2_2") (pintype "passive"))
      (node (ref "C3") (pin "2") (pinfunction "2_2") (pintype "passive"))
      (node (ref "C4") (pin "2") (pinfunction "2_2") (pintype "passive"))
      (node (ref "C6") (pin "2") (pinfunction "2_2") (pintype "passive"))
      (node (ref "C7") (pin "2") (pinfunction "2_2") (pintype "passive"))
      (node (ref "C8") (pin "2") (pinfunction "2_2") (pintype "passive"))
      (node (ref "C9") (pin "2") (pinfunction "2_2") (pintype "passive"))
      (node (ref "D1") (pin "A") (pinfunction "A_A") (pintype "bidirectional"))
      (node (ref "D10") (pin "C") (pinfunction "C_C") (pintype "passive"))
      (node (ref "D11") (pin "2") (pinfunction "A_2") (pintype "bidirectional"))
      (node (ref "D2") (pin "A") (pinfunction "A_A") (pintype "bidirectional"))
      (node (ref "D3") (pin "A") (pinfunction "A_A") (pintype "bidirectional"))
      (node (ref "D4") (pin "A") (pinfunction "A_A") (pintype "bidirectional"))
      (node (ref "D5") (pin "2") (pinfunction "A_2") (pintype "bidirectional"))
      (node (ref "DISP1") (pin "GND") (pinfunction "GND_GND") (pintype "bidirectional"))
      (node (ref "GND") (pin "1") (pinfunction "P$1_1") (pintype "bidirectional"))
      (node (ref "IC1") (pin "11") (pinfunction "A0_11") (pintype "input"))
      (node (ref "IC1") (pin "12") (pinfunction "A1_12") (pintype "input"))
      (node (ref "IC1") (pin "13") (pinfunction "A2_13") (pintype "input"))
      (node (ref "IC1") (pin "6") (pinfunction "VSS_6") (pintype "power_in"))
      (node (ref "JP3") (pin "2") (pinfunction "2_2") (pintype "passive"))
      (node (ref "K1") (pin "14@1") (pinfunction "NO_14@1") (pintype "passive"))
      (node (ref "K1") (pin "14@2") (pinfunction "NO_14@2") (pintype "passive"))
      (node (ref "PANEL") (pin "1") (pinfunction "1_1") (pintype "passive"))
      (node (ref "PHOTOCELL") (pin "1") (pinfunction "1_1") (pintype "passive"))
      (node (ref "Q1") (pin "1") (pinfunction "1_1") (pintype "passive"))
      (node (ref "Q2") (pin "1") (pinfunction "1_1") (pintype "passive"))
      (node (ref "Q3") (pin "1") (pinfunction "1_1") (pintype "passive"))
      (node (ref "Q4") (pin "1") (pinfunction "1_1") (pintype "passive"))
      (node (ref "Q5") (pin "1") (pinfunction "1_1") (pintype "passive"))
      (node (ref "Q6") (pin "1") (pinfunction "1_1") (pintype "passive"))
      (node (ref "Q7") (pin "1") (pinfunction "1_1") (pintype "passive"))
      (node (ref "Q8") (pin "1") (pinfunction "1_1") (pintype "passive"))
      (node (ref "R12") (pin "1") (pinfunction "1_1") (pintype "passive"))
      (node (ref "R13") (pin "1") (pinfunction "1_1") (pintype "passive"))
      (node (ref "R17") (pin "1") (pinfunction "1_1") (pintype "passive"))
      (node (ref "R2") (pin "1") (pinfunction "1_1") (pintype "passive"))
      (node (ref "R21") (pin "1") (pinfunction "1_1") (pintype "passive"))
      (node (ref "R23") (pin "1") (pinfunction "1_1") (pintype "passive"))
      (node (ref "R27") (pin "1") (pinfunction "1_1") (pintype "passive"))
      (node (ref "R29") (pin "1") (pinfunction "1_1") (pintype "passive"))
      (node (ref "R35") (pin "1") (pinfunction "1_1") (pintype "passive"))
      (node (ref "R8") (pin "2") (pinfunction "2_2") (pintype "passive"))
      (node (ref "STRING") (pin "1") (pinfunction "1_1") (pintype "passive"))
      (node (ref "U1") (pin "5") (pinfunction "GND_5") (pintype "bidirectional"))
      (node (ref "U10") (pin "2") (pinfunction "GND_2") (pintype "power_in"))
      (node (ref "U11") (pin "4") (pinfunction "GND_4") (pintype "bidirectional"))
      (node (ref "U12") (pin "GND") (pinfunction "GND_GND") (pintype "bidirectional"))
      (node (ref "U2") (pin "4") (pinfunction "V-_4") (pintype "power_in"))
      (node (ref "U3") (pin "2") (pinfunction "VSS_2") (pintype "bidirectional"))
      (node (ref "U3") (pin "6") (pinfunction "AO_6") (pintype "bidirectional"))
      (node (ref "U4") (pin "4") (pinfunction "V-_4") (pintype "power_in"))
      (node (ref "U5") (pin "1") (pinfunction "GND_1") (pintype "bidirectional"))
      (node (ref "U6") (pin "5") (pinfunction "NTC_5") (pintype "bidirectional"))
      (node (ref "U6") (pin "6") (pinfunction "TIMER_6") (pintype "bidirectional"))
      (node (ref "U6") (pin "EXP") (pinfunction "GND_EXP") (pintype "bidirectional"))
      (node (ref "U7") (pin "6") (pinfunction "~{E}_6") (pintype "input"))
      (node (ref "U7") (pin "7") (pinfunction "VEE_7") (pintype "bidirectional"))
      (node (ref "U7") (pin "8") (pinfunction "GND_8") (pintype "bidirectional"))
      (node (ref "U8") (pin "1") (pinfunction "GND_1") (pintype "bidirectional"))
      (node (ref "U9") (pin "GND") (pinfunction "GND_GND") (pintype "bidirectional"))
    )
    (net (code "11") (name "I2C_SCL") (class "Default")
      (node (ref "A1") (pin "9") (pinfunction "P$9_9") (pintype "bidirectional"))
      (node (ref "IC1") (pin "8") (pinfunction "SCL_8") (pintype "input"))
      (node (ref "JP3") (pin "3") (pinfunction "3_3") (pintype "passive"))
      (node (ref "R6") (pin "1") (pinfunction "1_1") (pintype "passive"))
      (node (ref "SCL") (pin "1") (pinfunction "P$1_1") (pintype "bidirectional"))
      (node (ref "U11") (pin "6") (pinfunction "SCL_6") (pintype "bidirectional"))
      (node (ref "U3") (pin "5") (pinfunction "SCL_5") (pintype "bidirectional"))
    )
    (net (code "12") (name "I2C_SDA") (class "Default")
      (node (ref "A1") (pin "10") (pinfunction "P$10_10") (pintype "bidirectional"))
      (node (ref "IC1") (pin "9") (pinfunction "SDA_9") (pintype "bidirectional"))
      (node (ref "JP3") (pin "4") (pinfunction "4_4") (pintype "passive"))
      (node (ref "R33") (pin "1") (pinfunction "1_1") (pintype "passive"))
      (node (ref "SDA") (pin "1") (pinfunction "P$1_1") (pintype "bidirectional"))
      (node (ref "U11") (pin "5") (pinfunction "SDA_5") (pintype "bidirectional"))
      (node (ref "U3") (pin "4") (pinfunction "SDA_4") (pintype "bidirectional"))
    )
    (net (code "13") (name "IPANELSCALED") (class "Default")
      (node (ref "A1") (pin "2") (pinfunction "P$2_2") (pintype "bidirectional"))
      (node (ref "D3") (pin "C") (pinfunction "C_C") (pintype "bidirectional"))
      (node (ref "R7") (pin "2") (pinfunction "2_2") (pintype "passive"))
    )
    (net (code "14") (name "IRRECEIVER") (class "Default")
      (node (ref "A1") (pin "32") (pinfunction "P$32_32") (pintype "bidirectional"))
      (node (ref "U12") (pin "OUT") (pinfunction "VOUT_OUT") (pintype "bidirectional"))
      (node (ref "U9") (pin "VOUT") (pinfunction "VOUT_VOUT") (pintype "bidirectional"))
    )
    (net (code "15") (name "Net-(C25-1)") (class "Default")
      (node (ref "C25") (pin "+") (pinfunction "1_+") (pintype "passive"))
      (node (ref "U11") (pin "3") (pinfunction "VBACKUP_3") (pintype "bidirectional"))
    )
    (net (code "16") (name "Net-(D5-C)") (class "Default")
      (node (ref "C20") (pin "1") (pinfunction "1_1") (pintype "passive"))
      (node (ref "D5") (pin "1") (pinfunction "C_1") (pintype "bidirectional"))
      (node (ref "R31") (pin "2") (pinfunction "2_2") (pintype "passive"))
      (node (ref "R32") (pin "1") (pinfunction "1_1") (pintype "passive"))
    )
    (net (code "17") (name "Net-(D10-PadA)") (class "Default")
      (node (ref "D10") (pin "A") (pinfunction "A_A") (pintype "passive"))
      (node (ref "R25") (pin "1") (pinfunction "1_1") (pintype "passive"))
    )
    (net (code "18") (name "Net-(D11-C)") (class "Default")
      (node (ref "C8") (pin "1") (pinfunction "1_1") (pintype "passive"))
      (node (ref "D11") (pin "1") (pinfunction "C_1") (pintype "bidirectional"))
      (node (ref "R5") (pin "1") (pinfunction "1_1") (pintype "passive"))
      (node (ref "U2") (pin "3") (pinfunction "IN+_3") (pintype "input"))
    )
    (net (code "19") (name "Net-(DACOUT-P$1)") (class "Default")
      (node (ref "DACOUT") (pin "1") (pinfunction "P$1_1") (pintype "bidirectional"))
      (node (ref "R10") (pin "2") (pinfunction "2_2") (pintype "passive"))
      (node (ref "U3") (pin "1") (pinfunction "VOUT_1") (pintype "bidirectional"))
    )
    (net (code "20") (name "Net-(F1-P$2-Pad2@1)") (class "Default")
      (node (ref "F1") (pin "2@1") (pinfunction "P$2_2@1") (pintype "bidirectional"))
      (node (ref "F1") (pin "2@2") (pinfunction "P$2_2@2") (pintype "bidirectional"))
      (node (ref "PANEL") (pin "2") (pinfunction "2_2") (pintype "passive"))
    )
    (net (code "21") (name "Net-(IPANEL-P$1)") (class "Default")
      (node (ref "IPANEL") (pin "1") (pinfunction "P$1_1") (pintype "bidirectional"))
      (node (ref "R4") (pin "1") (pinfunction "1_1") (pintype "passive"))
      (node (ref "U1") (pin "7") (pinfunction "VIOUT_7") (pintype "bidirectional"))
    )
    (net (code "22") (name "Net-(K1A-W-Pad11@1)") (class "Default")
      (node (ref "K1") (pin "11@1") (pinfunction "W_11@1") (pintype "passive"))
      (node (ref "K1") (pin "11@2") (pinfunction "W_11@2") (pintype "passive"))
      (node (ref "STRING") (pin "2") (pinfunction "2_2") (pintype "passive"))
    )
    (net (code "23") (name "Net-(Q1-Pad3)") (class "Default")
      (node (ref "Q1") (pin "3") (pinfunction "3_3") (pintype "passive"))
      (node (ref "Q2") (pin "3") (pinfunction "3_3") (pintype "passive"))
      (node (ref "Q3") (pin "3") (pinfunction "3_3") (pintype "passive"))
      (node (ref "Q4") (pin "3") (pinfunction "3_3") (pintype "passive"))
      (node (ref "Q5") (pin "3") (pinfunction "3_3") (pintype "passive"))
      (node (ref "Q6") (pin "3") (pinfunction "3_3") (pintype "passive"))
      (node (ref "Q7") (pin "3") (pinfunction "3_3") (pintype "passive"))
      (node (ref "Q8") (pin "3") (pinfunction "3_3") (pintype "passive"))
      (node (ref "R30") (pin "1") (pinfunction "1_1") (pintype "passive"))
    )
    (net (code "24") (name "Net-(U1-FILTER)") (class "Default")
      (node (ref "C1") (pin "1") (pinfunction "1_1") (pintype "passive"))
      (node (ref "U1") (pin "6") (pinfunction "FILTER_6") (pintype "bidirectional"))
    )
    (net (code "25") (name "Net-(U2-IN-)") (class "Default")
      (node (ref "C5") (pin "2") (pinfunction "2_2") (pintype "passive"))
      (node (ref "R3") (pin "1") (pinfunction "1_1") (pintype "passive"))
      (node (ref "R4") (pin "2") (pinfunction "2_2") (pintype "passive"))
      (node (ref "U2") (pin "2") (pinfunction "IN-_2") (pintype "input"))
    )
    (net (code "26") (name "Net-(U2-OUT)") (class "Default")
      (node (ref "C5") (pin "1") (pinfunction "1_1") (pintype "passive"))
      (node (ref "R3") (pin "2") (pinfunction "2_2") (pintype "passive"))
      (node (ref "R7") (pin "1") (pinfunction "1_1") (pintype "passive"))
      (node (ref "U2") (pin "6") (pinfunction "OUT_6") (pintype "output"))
    )
    (net (code "27") (name "Net-(U4-IN+)") (class "Default")
      (node (ref "R10") (pin "1") (pinfunction "1_1") (pintype "passive"))
      (node (ref "R31") (pin "1") (pinfunction "1_1") (pintype "passive"))
      (node (ref "U4") (pin "3") (pinfunction "IN+_3") (pintype "input"))
    )
    (net (code "28") (name "Net-(U4-IN-)") (class "Default")
      (node (ref "R8") (pin "1") (pinfunction "1_1") (pintype "passive"))
      (node (ref "R9") (pin "2") (pinfunction "2_2") (pintype "passive"))
      (node (ref "U4") (pin "2") (pinfunction "IN-_2") (pintype "input"))
    )
    (net (code "29") (name "Net-(U4-OUT)") (class "Default")
      (node (ref "R30") (pin "2") (pinfunction "2_2") (pintype "passive"))
      (node (ref "R9") (pin "1") (pinfunction "1_1") (pintype "passive"))
      (node (ref "U4") (pin "6") (pinfunction "OUT_6") (pintype "output"))
    )
    (net (code "30") (name "Net-(U5-T+)") (class "Default")
      (node (ref "TC-K") (pin "2") (pinfunction "2_2") (pintype "passive"))
      (node (ref "U5") (pin "3") (pinfunction "T+_3") (pintype "bidirectional"))
    )
    (net (code "31") (name "Net-(U5-T-)") (class "Default")
      (node (ref "TC-K") (pin "1") (pinfunction "1_1") (pintype "passive"))
      (node (ref "U5") (pin "2") (pinfunction "T-_2") (pintype "bidirectional"))
    )
    (net (code "32") (name "Net-(U6-FB)") (class "Default")
      (node (ref "R15") (pin "2") (pinfunction "2_2") (pintype "passive"))
      (node (ref "R16") (pin "1") (pinfunction "1_1") (pintype "passive"))
      (node (ref "U6") (pin "9") (pinfunction "FB_9") (pintype "bidirectional"))
    )
    (net (code "33") (name "Net-(U6-FBG)") (class "Default")
      (node (ref "R15") (pin "1") (pinfunction "1_1") (pintype "passive"))
      (node (ref "U6") (pin "8") (pinfunction "FBG_8") (pintype "bidirectional"))
    )
    (net (code "34") (name "Net-(U6-PROG)") (class "Default")
      (node (ref "R17") (pin "2") (pinfunction "2_2") (pintype "passive"))
      (node (ref "U6") (pin "3") (pinfunction "PROG_3") (pintype "bidirectional"))
    )
    (net (code "35") (name "Net-(U11-X1)") (class "Default")
      (node (ref "U11") (pin "1") (pinfunction "X1_1") (pintype "bidirectional"))
      (node (ref "Y1") (pin "1") (pinfunction "1_1") (pintype "passive"))
    )
    (net (code "36") (name "Net-(U11-X2)") (class "Default")
      (node (ref "U11") (pin "2") (pinfunction "X2_2") (pintype "bidirectional"))
      (node (ref "Y1") (pin "4") (pinfunction "2_4") (pintype "passive"))
    )
    (net (code "37") (name "ONEWIRE") (class "Default")
      (node (ref "1WIRE") (pin "2") (pinfunction "2_2") (pintype "passive"))
      (node (ref "A1") (pin "11") (pinfunction "P$11_11") (pintype "bidirectional"))
      (node (ref "R24") (pin "1") (pinfunction "1_1") (pintype "passive"))
    )
    (net (code "38") (name "PERIPHERALRESET") (class "Default")
      (node (ref "A1") (pin "31") (pinfunction "P$31_31") (pintype "bidirectional"))
      (node (ref "DISP1") (pin "RESET") (pinfunction "RESET_RESET") (pintype "bidirectional"))
      (node (ref "IC1") (pin "14") (pinfunction "~{RESET}_14") (pintype "input"))
      (node (ref "JP3") (pin "5") (pinfunction "5_5") (pintype "passive"))
      (node (ref "R35") (pin "2") (pinfunction "2_2") (pintype "passive"))
    )
    (net (code "39") (name "SDCD") (class "Default")
      (node (ref "A1") (pin "17") (pinfunction "P$17_17") (pintype "bidirectional"))
      (node (ref "DISP1") (pin "SDCD") (pinfunction "SDCD_SDCD") (pintype "bidirectional"))
    )
    (net (code "40") (name "SDCS") (class "Default")
      (node (ref "A1") (pin "8") (pinfunction "P$8_8") (pintype "bidirectional"))
      (node (ref "DISP1") (pin "SDCS") (pinfunction "SDCS_SDCS") (pintype "bidirectional"))
    )
    (net (code "41") (name "SPI_CLK") (class "Default")
      (node (ref "A1") (pin "7") (pinfunction "P$7_7") (pintype "bidirectional"))
      (node (ref "DISP1") (pin "SCK") (pinfunction "SCK_SCK") (pintype "bidirectional"))
      (node (ref "U5") (pin "5") (pinfunction "SCK_5") (pintype "bidirectional"))
    )
    (net (code "42") (name "SPI_MISO") (class "Default")
      (node (ref "A1") (pin "14") (pinfunction "P$14_14") (pintype "bidirectional"))
      (node (ref "DISP1") (pin "MISO") (pinfunction "MISO_MISO") (pintype "bidirectional"))
      (node (ref "U5") (pin "7") (pinfunction "SO_7") (pintype "bidirectional"))
    )
    (net (code "43") (name "SPI_MOSI") (class "Default")
      (node (ref "A1") (pin "15") (pinfunction "P$15_15") (pintype "bidirectional"))
      (node (ref "DISP1") (pin "MOSI") (pinfunction "MOSI_MOSI") (pintype "bidirectional"))
    )
    (net (code "44") (name "THERMOCOUPLECS") (class "Default")
      (node (ref "A1") (pin "19") (pinfunction "P$19_19") (pintype "bidirectional"))
      (node (ref "R34") (pin "1") (pinfunction "1_1") (pintype "passive"))
      (node (ref "U5") (pin "6") (pinfunction "/CS_6") (pintype "bidirectional"))
    )
    (net (code "45") (name "V3.3") (class "Default")
      (node (ref "1WIRE") (pin "3") (pinfunction "3_3") (pintype "passive"))
      (node (ref "A1") (pin "1") (pinfunction "P$1_1") (pintype "bidirectional"))
      (node (ref "C17") (pin "1") (pinfunction "1_1") (pintype "passive"))
      (node (ref "C21") (pin "1") (pinfunction "1_1") (pintype "passive"))
      (node (ref "C22") (pin "1") (pinfunction "1_1") (pintype "passive"))
      (node (ref "C23") (pin "1") (pinfunction "1_1") (pintype "passive"))
      (node (ref "C24") (pin "1") (pinfunction "1_1") (pintype "passive"))
      (node (ref "C6") (pin "1") (pinfunction "1_1") (pintype "passive"))
      (node (ref "C9") (pin "1") (pinfunction "1_1") (pintype "passive"))
      (node (ref "DISP1") (pin "VIN") (pinfunction "VIN_VIN") (pintype "bidirectional"))
      (node (ref "IC1") (pin "5") (pinfunction "VDD_5") (pintype "power_in"))
      (node (ref "JP3") (pin "1") (pinfunction "1_1") (pintype "passive"))
      (node (ref "R18") (pin "2") (pinfunction "2_2") (pintype "passive"))
      (node (ref "R19") (pin "2") (pinfunction "2_2") (pintype "passive"))
      (node (ref "R24") (pin "2") (pinfunction "2_2") (pintype "passive"))
      (node (ref "R28") (pin "2") (pinfunction "2_2") (pintype "passive"))
      (node (ref "R32") (pin "2") (pinfunction "2_2") (pintype "passive"))
      (node (ref "R33") (pin "2") (pinfunction "2_2") (pintype "passive"))
      (node (ref "R34") (pin "2") (pinfunction "2_2") (pintype "passive"))
      (node (ref "R6") (pin "2") (pinfunction "2_2") (pintype "passive"))
      (node (ref "U11") (pin "8") (pinfunction "VCC_8") (pintype "bidirectional"))
      (node (ref "U12") (pin "VCC") (pinfunction "VCC_VCC") (pintype "bidirectional"))
      (node (ref "U3") (pin "3") (pinfunction "VDD_3") (pintype "bidirectional"))
      (node (ref "U5") (pin "4") (pinfunction "VCC_4") (pintype "bidirectional"))
      (node (ref "U7") (pin "16") (pinfunction "VCC_16") (pintype "bidirectional"))
      (node (ref "U8") (pin "2") (pinfunction "VOUT_2") (pintype "bidirectional"))
      (node (ref "U9") (pin "VCC") (pinfunction "VCC_VCC") (pintype "bidirectional"))
    )
    (net (code "46") (name "V3P3SCALED") (class "Default")
      (node (ref "C14") (pin "1") (pinfunction "1_1") (pintype "passive"))
      (node (ref "R28") (pin "1") (pinfunction "1_1") (pintype "passive"))
      (node (ref "R29") (pin "2") (pinfunction "2_2") (pintype "passive"))
      (node (ref "U7") (pin "1") (pinfunction "Y4_1") (pintype "bidirectional"))
    )
    (net (code "47") (name "V5SW") (class "Default")
      (node (ref "C19") (pin "1") (pinfunction "1_1") (pintype "passive"))
      (node (ref "C3") (pin "1") (pinfunction "1_1") (pintype "passive"))
      (node (ref "C4") (pin "1") (pinfunction "1_1") (pintype "passive"))
      (node (ref "R11") (pin "2") (pinfunction "2_2") (pintype "passive"))
      (node (ref "R5") (pin "2") (pinfunction "2_2") (pintype "passive"))
      (node (ref "U1") (pin "8") (pinfunction "VCC_8") (pintype "bidirectional"))
      (node (ref "U10") (pin "5") (pinfunction "VOUT_5") (pintype "output"))
      (node (ref "U2") (pin "7") (pinfunction "V+_7") (pintype "power_in"))
    )
    (net (code "48") (name "V5SWENABLE") (class "Default")
      (node (ref "A1") (pin "3") (pinfunction "P$3_3") (pintype "bidirectional"))
      (node (ref "U10") (pin "3") (pinfunction "EN_3") (pintype "bidirectional"))
    )
    (net (code "49") (name "V5SWSCALED") (class "Default")
      (node (ref "C10") (pin "1") (pinfunction "1_1") (pintype "passive"))
      (node (ref "R11") (pin "1") (pinfunction "1_1") (pintype "passive"))
      (node (ref "R12") (pin "2") (pinfunction "2_2") (pintype "passive"))
      (node (ref "U7") (pin "5") (pinfunction "Y5_5") (pintype "bidirectional"))
    )
    (net (code "50") (name "VBATT1") (class "Default")
      (node (ref "BATT") (pin "3") (pinfunction "3_3") (pintype "passive"))
      (node (ref "R20") (pin "2") (pinfunction "2_2") (pintype "passive"))
      (node (ref "TP1") (pin "TP") (pinfunction "P$1_TP") (pintype "bidirectional"))
    )
    (net (code "51") (name "VBATT1SCALED") (class "Default")
      (node (ref "C11") (pin "1") (pinfunction "1_1") (pintype "passive"))
      (node (ref "R20") (pin "1") (pinfunction "1_1") (pintype "passive"))
      (node (ref "R21") (pin "2") (pinfunction "2_2") (pintype "passive"))
      (node (ref "U7") (pin "14") (pinfunction "Y1_14") (pintype "bidirectional"))
    )
    (net (code "52") (name "VBATT2") (class "Default")
      (node (ref "BATT") (pin "2") (pinfunction "2_2") (pintype "passive"))
      (node (ref "R22") (pin "2") (pinfunction "2_2") (pintype "passive"))
      (node (ref "TP2") (pin "TP") (pinfunction "P$1_TP") (pintype "bidirectional"))
    )
    (net (code "53") (name "VBATT2SCALED") (class "Default")
      (node (ref "C12") (pin "1") (pinfunction "1_1") (pintype "passive"))
      (node (ref "R22") (pin "1") (pinfunction "1_1") (pintype "passive"))
      (node (ref "R23") (pin "2") (pinfunction "2_2") (pintype "passive"))
      (node (ref "U7") (pin "15") (pinfunction "Y2_15") (pintype "bidirectional"))
    )
    (net (code "54") (name "VBATT3") (class "Default")
      (node (ref "BATT") (pin "1") (pinfunction "1_1") (pintype "passive"))
      (node (ref "C16") (pin "1") (pinfunction "1_1") (pintype "passive"))
      (node (ref "C18") (pin "1") (pinfunction "1_1") (pintype "passive"))
      (node (ref "C7") (pin "1") (pinfunction "1_1") (pintype "passive"))
      (node (ref "R16") (pin "2") (pinfunction "2_2") (pintype "passive"))
      (node (ref "R26") (pin "2") (pinfunction "2_2") (pintype "passive"))
      (node (ref "TP3") (pin "TP") (pinfunction "P$1_TP") (pintype "bidirectional"))
      (node (ref "U10") (pin "1") (pinfunction "VIN_1") (pintype "input"))
      (node (ref "U4") (pin "7") (pinfunction "V+_7") (pintype "power_in"))
      (node (ref "U6") (pin "10") (pinfunction "BAT_10") (pintype "bidirectional"))
      (node (ref "U8") (pin "3") (pinfunction "VIN_3") (pintype "bidirectional"))
    )
    (net (code "55") (name "VBATT3SCALED") (class "Default")
      (node (ref "C13") (pin "1") (pinfunction "1_1") (pintype "passive"))
      (node (ref "R26") (pin "1") (pinfunction "1_1") (pintype "passive"))
      (node (ref "R27") (pin "2") (pinfunction "2_2") (pintype "passive"))
      (node (ref "U7") (pin "12") (pinfunction "Y3_12") (pintype "bidirectional"))
    )
    (net (code "56") (name "VPANEL1") (class "Default")
      (node (ref "D1") (pin "C") (pinfunction "C_C") (pintype "bidirectional"))
      (node (ref "F1") (pin "1@1") (pinfunction "P$1_1@1") (pintype "bidirectional"))
      (node (ref "F1") (pin "1@2") (pinfunction "P$1_1@2") (pintype "bidirectional"))
      (node (ref "R1") (pin "2") (pinfunction "2_2") (pintype "passive"))
      (node (ref "U1") (pin "1") (pinfunction "IP+1_1") (pintype "bidirectional"))
      (node (ref "U1") (pin "2") (pinfunction "IP+2_2") (pintype "bidirectional"))
      (node (ref "VPANEL") (pin "1") (pinfunction "P$1_1") (pintype "bidirectional"))
    )
    (net (code "57") (name "VPANEL2") (class "Default")
      (node (ref "C15") (pin "1") (pinfunction "1_1") (pintype "passive"))
      (node (ref "K1") (pin "12@1") (pinfunction "NC_12@1") (pintype "passive"))
      (node (ref "K1") (pin "12@2") (pinfunction "NC_12@2") (pintype "passive"))
      (node (ref "Q1") (pin "2") (pinfunction "2_2") (pintype "passive"))
      (node (ref "Q2") (pin "2") (pinfunction "2_2") (pintype "passive"))
      (node (ref "Q3") (pin "2") (pinfunction "2_2") (pintype "passive"))
      (node (ref "Q4") (pin "2") (pinfunction "2_2") (pintype "passive"))
      (node (ref "Q5") (pin "2") (pinfunction "2_2") (pintype "passive"))
      (node (ref "Q6") (pin "2") (pinfunction "2_2") (pintype "passive"))
      (node (ref "Q7") (pin "2") (pinfunction "2_2") (pintype "passive"))
      (node (ref "Q8") (pin "2") (pinfunction "2_2") (pintype "passive"))
      (node (ref "R14") (pin "2") (pinfunction "2_2") (pintype "passive"))
      (node (ref "U1") (pin "3") (pinfunction "IP-1_3") (pintype "bidirectional"))
      (node (ref "U1") (pin "4") (pinfunction "IP-2_4") (pintype "bidirectional"))
      (node (ref "U6") (pin "1") (pinfunction "IN_1") (pintype "bidirectional"))
    )
    (net (code "58") (name "VPANELSCALED") (class "Default")
      (node (ref "A1") (pin "6") (pinfunction "P$6_6") (pintype "bidirectional"))
      (node (ref "C2") (pin "1") (pinfunction "1_1") (pintype "passive"))
      (node (ref "D2") (pin "C") (pinfunction "C_C") (pintype "bidirectional"))
      (node (ref "R1") (pin "1") (pinfunction "1_1") (pintype "passive"))
      (node (ref "R2") (pin "2") (pinfunction "2_2") (pintype "passive"))
    )
    (net (code "59") (name "unconnected-(A1-P$12-Pad12)") (class "Default")
      (node (ref "A1") (pin "12") (pinfunction "P$12_12") (pintype "bidirectional"))
    )
    (net (code "60") (name "unconnected-(A1-P$16-Pad16)") (class "Default")
      (node (ref "A1") (pin "16") (pinfunction "P$16_16") (pintype "bidirectional"))
    )
    (net (code "61") (name "unconnected-(A1-P$21-Pad21)") (class "Default")
      (node (ref "A1") (pin "21") (pinfunction "P$21_21") (pintype "bidirectional"))
    )
    (net (code "62") (name "unconnected-(A1-P$23-Pad23)") (class "Default")
      (node (ref "A1") (pin "23") (pinfunction "P$23_23") (pintype "bidirectional"))
    )
    (net (code "63") (name "unconnected-(A1-P$25-Pad25)") (class "Default")
      (node (ref "A1") (pin "25") (pinfunction "P$25_25") (pintype "bidirectional"))
    )
    (net (code "64") (name "unconnected-(A1-P$26-Pad26)") (class "Default")
      (node (ref "A1") (pin "26") (pinfunction "P$26_26") (pintype "bidirectional"))
    )
    (net (code "65") (name "unconnected-(A1-P$33-Pad33)") (class "Default")
      (node (ref "A1") (pin "33") (pinfunction "P$33_33") (pintype "bidirectional"))
    )
    (net (code "66") (name "unconnected-(A1-P$34-Pad34)") (class "Default")
      (node (ref "A1") (pin "34") (pinfunction "P$34_34") (pintype "bidirectional"))
    )
    (net (code "67") (name "unconnected-(A1-P$35-Pad35)") (class "Default")
      (node (ref "A1") (pin "35") (pinfunction "P$35_35") (pintype "bidirectional"))
    )
    (net (code "68") (name "unconnected-(A1-P$36-Pad36)") (class "Default")
      (node (ref "A1") (pin "36") (pinfunction "P$36_36") (pintype "bidirectional"))
    )
    (net (code "69") (name "unconnected-(A1-P$37-Pad37)") (class "Default")
      (node (ref "A1") (pin "37") (pinfunction "P$37_37") (pintype "bidirectional"))
    )
    (net (code "70") (name "unconnected-(A1-P$38-Pad38)") (class "Default")
      (node (ref "A1") (pin "38") (pinfunction "P$38_38") (pintype "bidirectional"))
    )
    (net (code "71") (name "unconnected-(A1-P$39-Pad39)") (class "Default")
      (node (ref "A1") (pin "39") (pinfunction "P$39_39") (pintype "bidirectional"))
    )
    (net (code "72") (name "unconnected-(A1-P$40-Pad40)") (class "Default")
      (node (ref "A1") (pin "40") (pinfunction "P$40_40") (pintype "bidirectional"))
    )
    (net (code "73") (name "unconnected-(D5-NC-Pad3)") (class "Default")
      (node (ref "D5") (pin "3") (pinfunction "NC_3") (pintype "bidirectional"))
    )
    (net (code "74") (name "unconnected-(D11-NC-Pad3)") (class "Default")
      (node (ref "D11") (pin "3") (pinfunction "NC_3") (pintype "bidirectional"))
    )
    (net (code "75") (name "unconnected-(DISP1-Pad3VO)") (class "Default")
      (node (ref "DISP1") (pin "3VO") (pinfunction "3VO_3VO") (pintype "bidirectional"))
    )
    (net (code "76") (name "unconnected-(IC1-GPA0-Pad17)") (class "Default")
      (node (ref "IC1") (pin "17") (pinfunction "GPA0_17") (pintype "bidirectional"))
    )
    (net (code "77") (name "unconnected-(IC1-GPA1-Pad18)") (class "Default")
      (node (ref "IC1") (pin "18") (pinfunction "GPA1_18") (pintype "bidirectional"))
    )
    (net (code "78") (name "unconnected-(IC1-GPA2-Pad19)") (class "Default")
      (node (ref "IC1") (pin "19") (pinfunction "GPA2_19") (pintype "bidirectional"))
    )
    (net (code "79") (name "unconnected-(IC1-GPA3-Pad20)") (class "Default")
      (node (ref "IC1") (pin "20") (pinfunction "GPA3_20") (pintype "bidirectional"))
    )
    (net (code "80") (name "unconnected-(IC1-GPA4-Pad21)") (class "Default")
      (node (ref "IC1") (pin "21") (pinfunction "GPA4_21") (pintype "bidirectional"))
    )
    (net (code "81") (name "unconnected-(IC1-GPA5-Pad22)") (class "Default")
      (node (ref "IC1") (pin "22") (pinfunction "GPA5_22") (pintype "bidirectional"))
    )
    (net (code "82") (name "unconnected-(IC1-GPA6-Pad23)") (class "Default")
      (node (ref "IC1") (pin "23") (pinfunction "GPA6_23") (pintype "bidirectional"))
    )
    (net (code "83") (name "unconnected-(IC1-GPA7-Pad24)") (class "Default")
      (node (ref "IC1") (pin "24") (pinfunction "GPA7_24") (pintype "bidirectional"))
    )
    (net (code "84") (name "unconnected-(IC1-GPB0-Pad25)") (class "Default")
      (node (ref "IC1") (pin "25") (pinfunction "GPB0_25") (pintype "bidirectional"))
    )
    (net (code "85") (name "unconnected-(IC1-GPB1-Pad26)") (class "Default")
      (node (ref "IC1") (pin "26") (pinfunction "GPB1_26") (pintype "bidirectional"))
    )
    (net (code "86") (name "unconnected-(IC1-GPB2-Pad27)") (class "Default")
      (node (ref "IC1") (pin "27") (pinfunction "GPB2_27") (pintype "bidirectional"))
    )
    (net (code "87") (name "unconnected-(IC1-GPB3-Pad28)") (class "Default")
      (node (ref "IC1") (pin "28") (pinfunction "GPB3_28") (pintype "bidirectional"))
    )
    (net (code "88") (name "unconnected-(IC1-GPB4-Pad1)") (class "Default")
      (node (ref "IC1") (pin "1") (pinfunction "GPB4_1") (pintype "bidirectional"))
    )
    (net (code "89") (name "unconnected-(IC1-GPB5-Pad2)") (class "Default")
      (node (ref "IC1") (pin "2") (pinfunction "GPB5_2") (pintype "bidirectional"))
    )
    (net (code "90") (name "unconnected-(IC1-GPB6-Pad3)") (class "Default")
      (node (ref "IC1") (pin "3") (pinfunction "GPB6_3") (pintype "bidirectional"))
    )
    (net (code "91") (name "unconnected-(IC1-GPB7-Pad4)") (class "Default")
      (node (ref "IC1") (pin "4") (pinfunction "GPB7_4") (pintype "bidirectional"))
    )
    (net (code "92") (name "unconnected-(IC1-INTA-Pad16)") (class "Default")
      (node (ref "IC1") (pin "16") (pinfunction "INTA_16") (pintype "output"))
    )
    (net (code "93") (name "unconnected-(IC1-INTB-Pad15)") (class "Default")
      (node (ref "IC1") (pin "15") (pinfunction "INTB_15") (pintype "output"))
    )
    (net (code "94") (name "unconnected-(K1-PadA1)") (class "Default")
      (node (ref "K1") (pin "A1") (pinfunction "A1_A1") (pintype "passive"))
    )
    (net (code "95") (name "unconnected-(K1-PadA2)") (class "Default")
      (node (ref "K1") (pin "A2") (pinfunction "A2_A2") (pintype "passive"))
    )
    (net (code "96") (name "unconnected-(K1-PadA3)") (class "Default")
      (node (ref "K1") (pin "A3") (pinfunction "A3_A3") (pintype "passive"))
    )
    (net (code "97") (name "unconnected-(U2-NC8-Pad5)") (class "Default")
      (node (ref "U2") (pin "5") (pinfunction "NC8_5") (pintype "passive"))
    )
    (net (code "98") (name "unconnected-(U2-ON1-Pad1)") (class "Default")
      (node (ref "U2") (pin "1") (pinfunction "ON1_1") (pintype "passive"))
    )
    (net (code "99") (name "unconnected-(U2-ON5-Pad8)") (class "Default")
      (node (ref "U2") (pin "8") (pinfunction "ON5_8") (pintype "passive"))
    )
    (net (code "100") (name "unconnected-(U4-NC8-Pad5)") (class "Default")
      (node (ref "U4") (pin "5") (pinfunction "NC8_5") (pintype "passive"))
    )
    (net (code "101") (name "unconnected-(U4-ON1-Pad1)") (class "Default")
      (node (ref "U4") (pin "1") (pinfunction "ON1_1") (pintype "passive"))
    )
    (net (code "102") (name "unconnected-(U4-ON5-Pad8)") (class "Default")
      (node (ref "U4") (pin "8") (pinfunction "ON5_8") (pintype "passive"))
    )
    (net (code "103") (name "unconnected-(U5-NC-Pad8)") (class "Default")
      (node (ref "U5") (pin "8") (pinfunction "NC_8") (pintype "bidirectional"))
    )
    (net (code "104") (name "unconnected-(U6-NTCBIAS-Pad4)") (class "Default")
      (node (ref "U6") (pin "4") (pinfunction "NTCBIAS_4") (pintype "bidirectional"))
    )
    (net (code "105") (name "unconnected-(U7-Y6-Pad2)") (class "Default")
      (node (ref "U7") (pin "2") (pinfunction "Y6_2") (pintype "bidirectional"))
    )
    (net (code "106") (name "unconnected-(U7-Y7-Pad4)") (class "Default")
      (node (ref "U7") (pin "4") (pinfunction "Y7_4") (pintype "bidirectional"))
    )
    (net (code "107") (name "unconnected-(U10-BYP{slash}ADJ-Pad4)") (class "Default")
      (node (ref "U10") (pin "4") (pinfunction "BYP/ADJ_4") (pintype "bidirectional"))
    )
    (net (code "108") (name "unconnected-(U11-SQW{slash}~{INT}-Pad7)") (class "Default")
      (node (ref "U11") (pin "7") (pinfunction "SQW/~{INT}_7") (pintype "bidirectional"))
    )
    (net (code "109") (name "~{BATTCHARGING}") (class "Default")
      (node (ref "A1") (pin "4") (pinfunction "P$4_4") (pintype "bidirectional"))
      (node (ref "R18") (pin "1") (pinfunction "1_1") (pintype "passive"))
      (node (ref "U6") (pin "7") (pinfunction "~{CHRG}_7") (pintype "bidirectional"))
    )
  )
)
